# ATTAMI-Shield-tinyISP.net
KiCad netlist of a schematic drawn in EAGLE
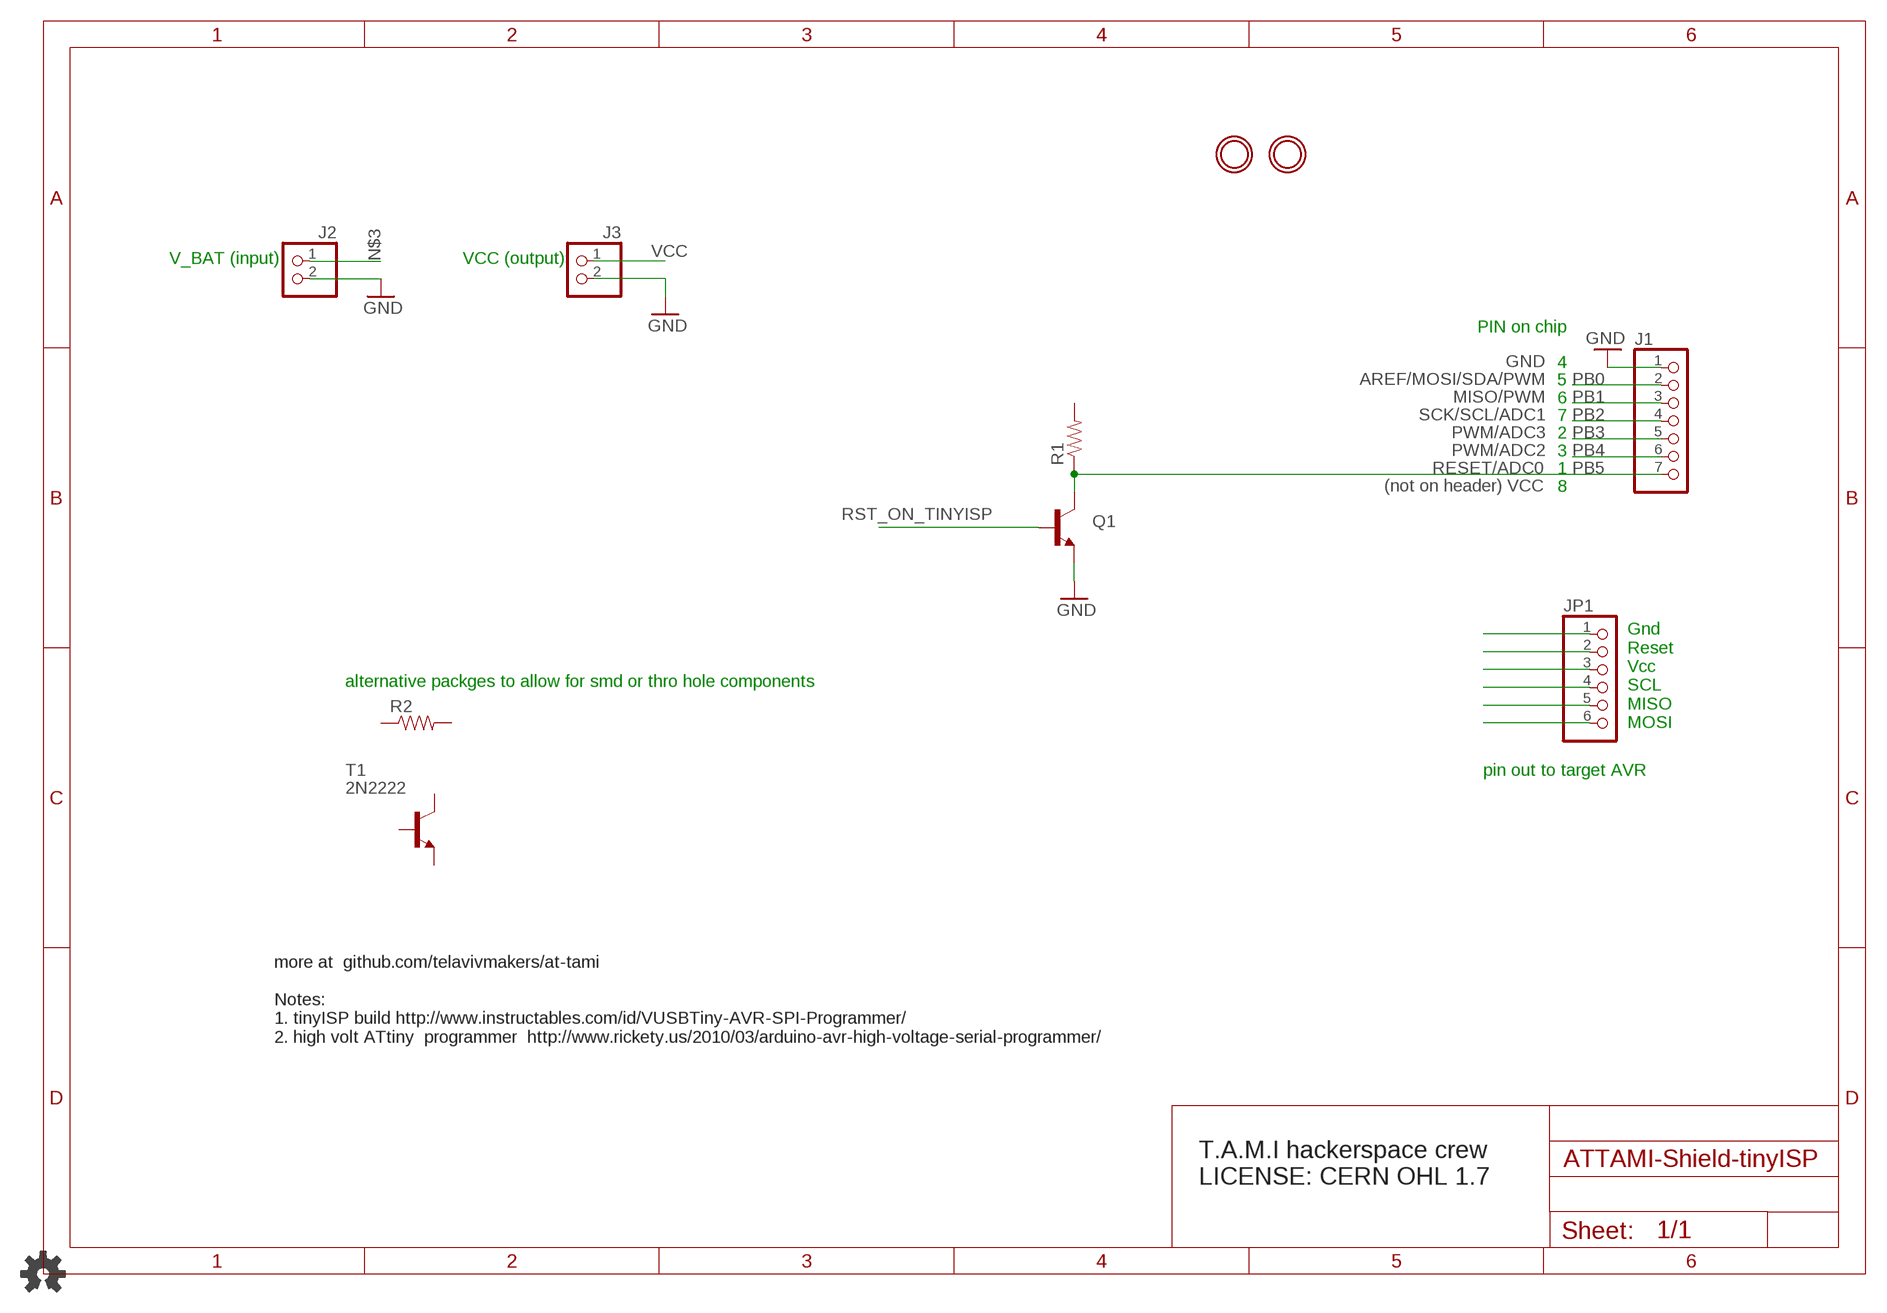
[diagram p0: schematic, sheet 1]

(export (version "E")
  (design (tool "Eeschema 10.0.6"))
  (components
    (comp (ref "J1")
      (value "HEADER-1X7ROUND")
      (footprint "eagle-import:1X07_ROUND")
      (libsource (lib "eagle-import") (part "HEADER-1X7ROUND"))
    )
    (comp (ref "J2")
      (value "HEADER-1X2ROUND")
      (footprint "eagle-import:1X02_ROUND")
      (libsource (lib "eagle-import") (part "HEADER-1X2ROUND"))
    )
    (comp (ref "J3")
      (value "HEADER-1X2ROUND")
      (footprint "eagle-import:1X02_ROUND")
      (libsource (lib "eagle-import") (part "HEADER-1X2ROUND"))
    )
    (comp (ref "JP1")
      (value "HEADER-1X6ROUND")
      (footprint "eagle-import:1X06_ROUND")
      (libsource (lib "eagle-import") (part "HEADER-1X6ROUND"))
    )
    (comp (ref "Q1")
      (value "TRANSISTOR_NPNSOT23")
      (footprint "eagle-import:SOT23")
      (libsource (lib "eagle-import") (part "TRANSISTOR_NPNSOT23"))
    )
    (comp (ref "R1")
      (value "RESISTOR0805-RES")
      (footprint "eagle-import:0805")
      (libsource (lib "eagle-import") (part "RESISTOR0805-RES"))
    )
    (comp (ref "R2")
      (value "RESISTORAXIAL-0.3")
      (footprint "eagle-import:AXIAL-0.3")
      (libsource (lib "eagle-import") (part "RESISTORAXIAL-0.3"))
    )
    (comp (ref "T1")
      (value "2N2222")
      (footprint "eagle-import:TO92-EBC-OVAL")
      (libsource (lib "eagle-import") (part "2N2222"))
    )
    (comp (ref "U$1")
      (value "MOUNTINGHOLE2.0")
      (footprint "eagle-import:MOUNTINGHOLE_2.0_PLATED")
      (libsource (lib "eagle-import") (part "MOUNTINGHOLE2.0"))
    )
    (comp (ref "U$2")
      (value "MOUNTINGHOLE2.0")
      (footprint "eagle-import:MOUNTINGHOLE_2.0_PLATED")
      (libsource (lib "eagle-import") (part "MOUNTINGHOLE2.0"))
    )
  )
  (nets
    (net (code "1") (name "/N$3") (class "Default")
      (node (ref "J2") (pin "1") (pinfunction "1_1") (pintype "passive"))
    )
    (net (code "2") (name "/PB0") (class "Default")
      (node (ref "J1") (pin "2") (pinfunction "2_2") (pintype "passive"))
    )
    (net (code "3") (name "/PB1") (class "Default")
      (node (ref "J1") (pin "3") (pinfunction "3_3") (pintype "passive"))
    )
    (net (code "4") (name "/PB2") (class "Default")
      (node (ref "J1") (pin "4") (pinfunction "4_4") (pintype "passive"))
    )
    (net (code "5") (name "/PB3") (class "Default")
      (node (ref "J1") (pin "5") (pinfunction "5_5") (pintype "passive"))
    )
    (net (code "6") (name "/PB4") (class "Default")
      (node (ref "J1") (pin "6") (pinfunction "6_6") (pintype "passive"))
    )
    (net (code "7") (name "/PB5") (class "Default")
      (node (ref "J1") (pin "7") (pinfunction "7_7") (pintype "passive"))
      (node (ref "Q1") (pin "3") (pinfunction "C_3") (pintype "passive"))
      (node (ref "R1") (pin "1") (pinfunction "1_1") (pintype "passive"))
    )
    (net (code "8") (name "/RST_ON_TINYISP") (class "Default")
      (node (ref "Q1") (pin "1") (pinfunction "B_1") (pintype "passive"))
    )
    (net (code "9") (name "/VCC") (class "Default")
      (node (ref "J3") (pin "1") (pinfunction "1_1") (pintype "passive"))
    )
    (net (code "10") (name "GND") (class "Default")
      (node (ref "J1") (pin "1") (pinfunction "1_1") (pintype "passive"))
      (node (ref "J2") (pin "2") (pinfunction "2_2") (pintype "passive"))
      (node (ref "J3") (pin "2") (pinfunction "2_2") (pintype "passive"))
      (node (ref "Q1") (pin "2") (pinfunction "E_2") (pintype "passive"))
    )
    (net (code "11") (name "unconnected-(JP1-Pad1)") (class "Default")
      (node (ref "JP1") (pin "1") (pinfunction "1_1") (pintype "passive"))
    )
    (net (code "12") (name "unconnected-(JP1-Pad2)") (class "Default")
      (node (ref "JP1") (pin "2") (pinfunction "2_2") (pintype "passive"))
    )
    (net (code "13") (name "unconnected-(JP1-Pad3)") (class "Default")
      (node (ref "JP1") (pin "3") (pinfunction "3_3") (pintype "passive"))
    )
    (net (code "14") (name "unconnected-(JP1-Pad4)") (class "Default")
      (node (ref "JP1") (pin "4") (pinfunction "4_4") (pintype "passive"))
    )
    (net (code "15") (name "unconnected-(JP1-Pad5)") (class "Default")
      (node (ref "JP1") (pin "5") (pinfunction "5_5") (pintype "passive"))
    )
    (net (code "16") (name "unconnected-(JP1-Pad6)") (class "Default")
      (node (ref "JP1") (pin "6") (pinfunction "6_6") (pintype "passive"))
    )
    (net (code "17") (name "unconnected-(R1-Pad2)") (class "Default")
      (node (ref "R1") (pin "2") (pinfunction "2_2") (pintype "passive"))
    )
    (net (code "18") (name "unconnected-(R2-1-PadP$1)") (class "Default")
      (node (ref "R2") (pin "P$1") (pinfunction "1_P$1") (pintype "passive"))
    )
    (net (code "19") (name "unconnected-(R2-2-PadP$2)") (class "Default")
      (node (ref "R2") (pin "P$2") (pinfunction "2_P$2") (pintype "passive"))
    )
    (net (code "20") (name "unconnected-(T1-PadB)") (class "Default")
      (node (ref "T1") (pin "B") (pinfunction "B_B") (pintype "passive"))
    )
    (net (code "21") (name "unconnected-(T1-PadC)") (class "Default")
      (node (ref "T1") (pin "C") (pinfunction "C_C") (pintype "passive"))
    )
    (net (code "22") (name "unconnected-(T1-PadE)") (class "Default")
      (node (ref "T1") (pin "E") (pinfunction "E_E") (pintype "passive"))
    )
  )
)
